# Pure_QUA_SMD_V2_1.net
KiCad netlist of a schematic drawn in EAGLE
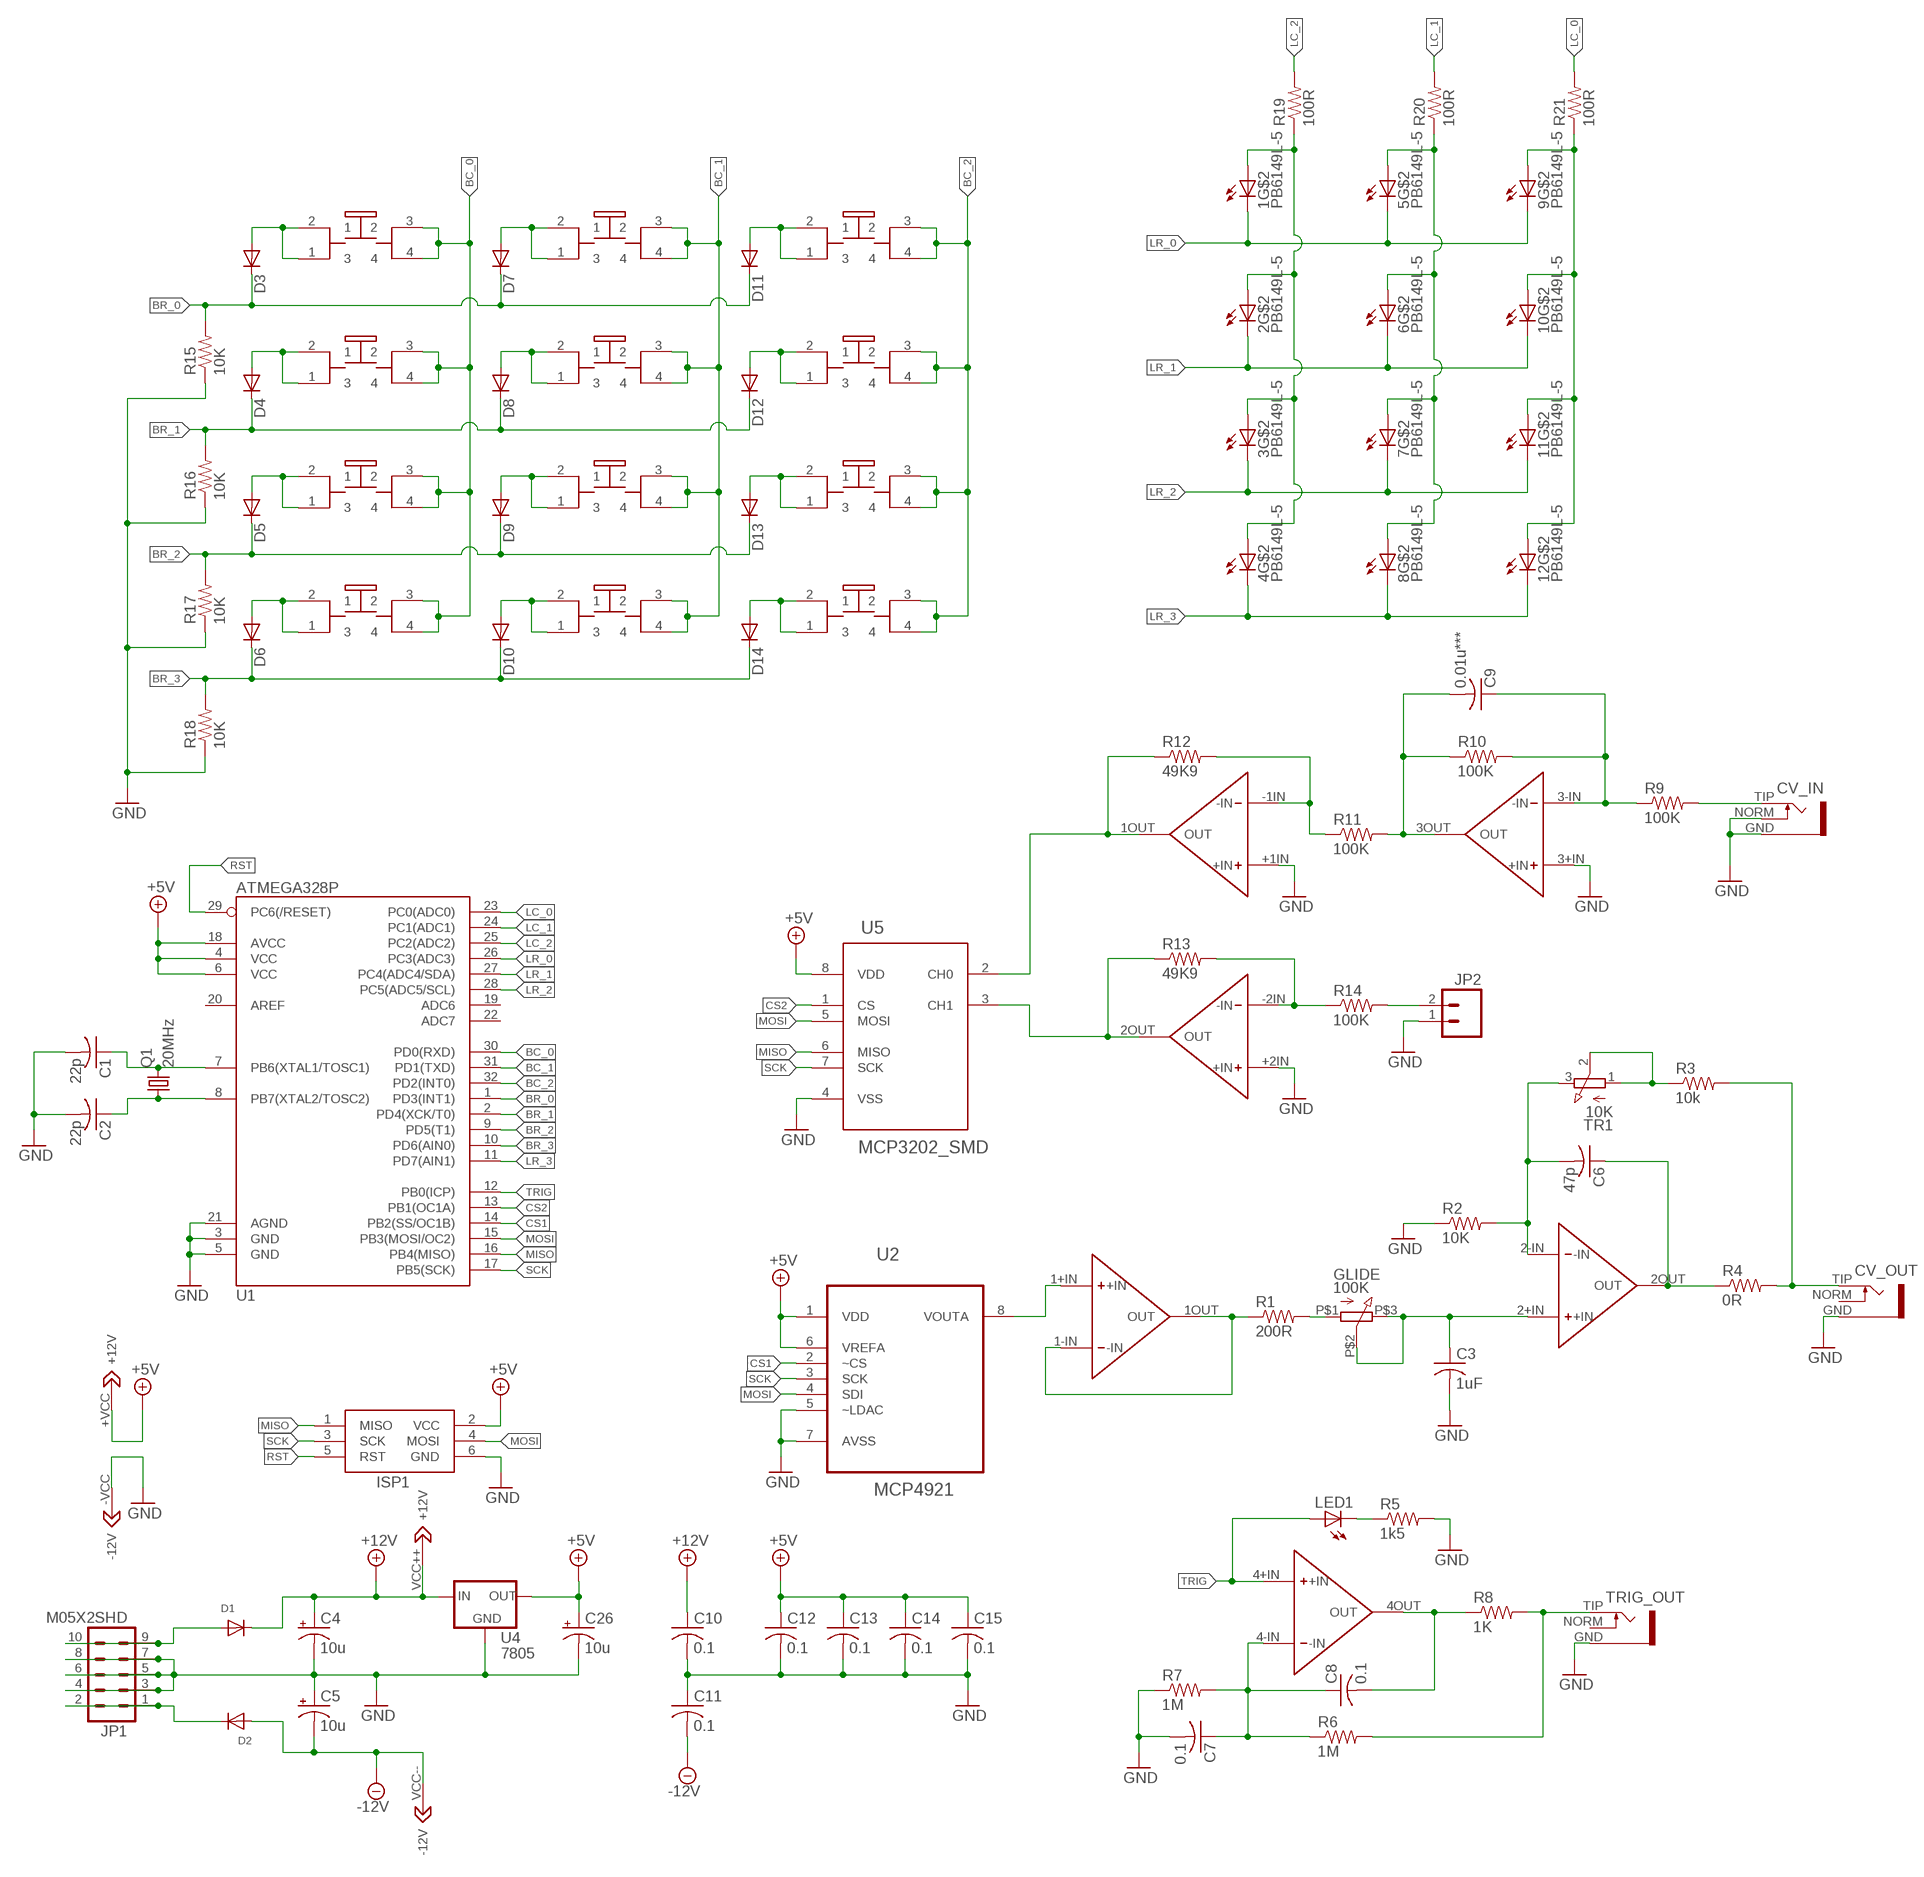
[diagram p0: schematic, sheet 1]

(export (version "E")
  (design (tool "Eeschema 10.0.6"))
  (components
    (comp (ref "1")
      (value "PB6149L-5")
      (footprint "eagle-import:PB6149L")
      (libsource (lib "eagle-import") (part "PB6149L-5"))
    )
    (comp (ref "2")
      (value "PB6149L-5")
      (footprint "eagle-import:PB6149L")
      (libsource (lib "eagle-import") (part "PB6149L-5"))
    )
    (comp (ref "3")
      (value "PB6149L-5")
      (footprint "eagle-import:PB6149L")
      (libsource (lib "eagle-import") (part "PB6149L-5"))
    )
    (comp (ref "4")
      (value "PB6149L-5")
      (footprint "eagle-import:PB6149L")
      (libsource (lib "eagle-import") (part "PB6149L-5"))
    )
    (comp (ref "5")
      (value "PB6149L-5")
      (footprint "eagle-import:PB6149L")
      (libsource (lib "eagle-import") (part "PB6149L-5"))
    )
    (comp (ref "6")
      (value "PB6149L-5")
      (footprint "eagle-import:PB6149L")
      (libsource (lib "eagle-import") (part "PB6149L-5"))
    )
    (comp (ref "7")
      (value "PB6149L-5")
      (footprint "eagle-import:PB6149L")
      (libsource (lib "eagle-import") (part "PB6149L-5"))
    )
    (comp (ref "8")
      (value "PB6149L-5")
      (footprint "eagle-import:PB6149L")
      (libsource (lib "eagle-import") (part "PB6149L-5"))
    )
    (comp (ref "9")
      (value "PB6149L-5")
      (footprint "eagle-import:PB6149L")
      (libsource (lib "eagle-import") (part "PB6149L-5"))
    )
    (comp (ref "10")
      (value "PB6149L-5")
      (footprint "eagle-import:PB6149L")
      (libsource (lib "eagle-import") (part "PB6149L-5"))
    )
    (comp (ref "11")
      (value "PB6149L-5")
      (footprint "eagle-import:PB6149L")
      (libsource (lib "eagle-import") (part "PB6149L-5"))
    )
    (comp (ref "12")
      (value "PB6149L-5")
      (footprint "eagle-import:PB6149L")
      (libsource (lib "eagle-import") (part "PB6149L-5"))
    )
    (comp (ref "C1")
      (value "22p")
      (footprint "eagle-import:C0805K")
      (libsource (lib "eagle-import") (part "C-USC0805K"))
    )
    (comp (ref "C2")
      (value "22p")
      (footprint "eagle-import:C0805K")
      (libsource (lib "eagle-import") (part "C-USC0805K"))
    )
    (comp (ref "C3")
      (value "1uF")
      (footprint "eagle-import:C0805K")
      (libsource (lib "eagle-import") (part "C-USC0805K"))
    )
    (comp (ref "C4")
      (value "10u")
      (footprint "eagle-import:153CLV-0505")
      (libsource (lib "eagle-import") (part "CPOL-US153CLV-0505"))
    )
    (comp (ref "C5")
      (value "10u")
      (footprint "eagle-import:153CLV-0505")
      (libsource (lib "eagle-import") (part "CPOL-US153CLV-0505"))
    )
    (comp (ref "C6")
      (value "47p")
      (footprint "eagle-import:C0805K")
      (libsource (lib "eagle-import") (part "C-USC0805K"))
    )
    (comp (ref "C7")
      (value "0.1")
      (footprint "eagle-import:C0805K")
      (libsource (lib "eagle-import") (part "C-USC0805K"))
    )
    (comp (ref "C8")
      (value "0.1")
      (footprint "eagle-import:C0805K")
      (libsource (lib "eagle-import") (part "C-USC0805K"))
    )
    (comp (ref "C9")
      (value "0.01u***")
      (footprint "eagle-import:C0805K")
      (libsource (lib "eagle-import") (part "C-USC0805K"))
    )
    (comp (ref "C10")
      (value "0.1")
      (footprint "eagle-import:C0805K")
      (libsource (lib "eagle-import") (part "C-USC0805K"))
    )
    (comp (ref "C11")
      (value "0.1")
      (footprint "eagle-import:C0805K")
      (libsource (lib "eagle-import") (part "C-USC0805K"))
    )
    (comp (ref "C12")
      (value "0.1")
      (footprint "eagle-import:C0805K")
      (libsource (lib "eagle-import") (part "C-USC0805K"))
    )
    (comp (ref "C13")
      (value "0.1")
      (footprint "eagle-import:C0805K")
      (libsource (lib "eagle-import") (part "C-USC0805K"))
    )
    (comp (ref "C14")
      (value "0.1")
      (footprint "eagle-import:C0805K")
      (libsource (lib "eagle-import") (part "C-USC0805K"))
    )
    (comp (ref "C15")
      (value "0.1")
      (footprint "eagle-import:C0805K")
      (libsource (lib "eagle-import") (part "C-USC0805K"))
    )
    (comp (ref "C26")
      (value "10u")
      (footprint "eagle-import:153CLV-0505")
      (libsource (lib "eagle-import") (part "CPOL-US153CLV-0505"))
    )
    (comp (ref "CV_IN")
      (value "S_JACK")
      (footprint "eagle-import:S_JACK")
      (libsource (lib "eagle-import") (part "S_JACK"))
    )
    (comp (ref "CV_OUT")
      (value "S_JACK")
      (footprint "eagle-import:S_JACK")
      (libsource (lib "eagle-import") (part "S_JACK"))
    )
    (comp (ref "D1")
      (value "DIODESMA")
      (footprint "eagle-import:SMADIODE")
      (libsource (lib "eagle-import") (part "adafruit_DIODESMA"))
    )
    (comp (ref "D2")
      (value "DIODESMA")
      (footprint "eagle-import:SMADIODE")
      (libsource (lib "eagle-import") (part "adafruit_DIODESMA"))
    )
    (comp (ref "D3")
      (value "DIODESOD")
      (footprint "eagle-import:SOD-323")
      (libsource (lib "eagle-import") (part "DIODESOD"))
    )
    (comp (ref "D4")
      (value "DIODESOD")
      (footprint "eagle-import:SOD-323")
      (libsource (lib "eagle-import") (part "DIODESOD"))
    )
    (comp (ref "D5")
      (value "DIODESOD")
      (footprint "eagle-import:SOD-323")
      (libsource (lib "eagle-import") (part "DIODESOD"))
    )
    (comp (ref "D6")
      (value "DIODESOD")
      (footprint "eagle-import:SOD-323")
      (libsource (lib "eagle-import") (part "DIODESOD"))
    )
    (comp (ref "D7")
      (value "DIODESOD")
      (footprint "eagle-import:SOD-323")
      (libsource (lib "eagle-import") (part "DIODESOD"))
    )
    (comp (ref "D8")
      (value "DIODESOD")
      (footprint "eagle-import:SOD-323")
      (libsource (lib "eagle-import") (part "DIODESOD"))
    )
    (comp (ref "D9")
      (value "DIODESOD")
      (footprint "eagle-import:SOD-323")
      (libsource (lib "eagle-import") (part "DIODESOD"))
    )
    (comp (ref "D10")
      (value "DIODESOD")
      (footprint "eagle-import:SOD-323")
      (libsource (lib "eagle-import") (part "DIODESOD"))
    )
    (comp (ref "D11")
      (value "DIODESOD")
      (footprint "eagle-import:SOD-323")
      (libsource (lib "eagle-import") (part "DIODESOD"))
    )
    (comp (ref "D12")
      (value "DIODESOD")
      (footprint "eagle-import:SOD-323")
      (libsource (lib "eagle-import") (part "DIODESOD"))
    )
    (comp (ref "D13")
      (value "DIODESOD")
      (footprint "eagle-import:SOD-323")
      (libsource (lib "eagle-import") (part "DIODESOD"))
    )
    (comp (ref "D14")
      (value "DIODESOD")
      (footprint "eagle-import:SOD-323")
      (libsource (lib "eagle-import") (part "DIODESOD"))
    )
    (comp (ref "GLIDE")
      (value "100K")
      (footprint "eagle-import:Q-POT")
      (libsource (lib "eagle-import") (part "Q-POT"))
    )
    (comp (ref "ISP1")
      (value "AVRISP-6")
      (footprint "eagle-import:AVRISP")
      (libsource (lib "eagle-import") (part "AVRISP-6"))
    )
    (comp (ref "JP1")
      (value "M05X2SHD")
      (footprint "eagle-import:2X5-SHROUDED")
      (libsource (lib "eagle-import") (part "M05X2SHD"))
    )
    (comp (ref "JP2")
      (value "M02PTH")
      (footprint "eagle-import:1X02")
      (libsource (lib "eagle-import") (part "M02PTH"))
    )
    (comp (ref "LED1")
      (value "LED5MM")
      (footprint "eagle-import:LED5MM")
      (libsource (lib "eagle-import") (part "LED5MM"))
    )
    (comp (ref "Q1")
      (value "20MHz")
      (footprint "eagle-import:HC49UP")
      (libsource (lib "eagle-import") (part "CRYSTALHC49UP"))
    )
    (comp (ref "R1")
      (value "200R")
      (footprint "eagle-import:R0805")
      (libsource (lib "eagle-import") (part "R-US_R0805"))
    )
    (comp (ref "R2")
      (value "10K")
      (footprint "eagle-import:R0805")
      (libsource (lib "eagle-import") (part "R-US_R0805"))
    )
    (comp (ref "R3")
      (value "10k")
      (footprint "eagle-import:R0805")
      (libsource (lib "eagle-import") (part "R-US_R0805"))
    )
    (comp (ref "R4")
      (value "0R")
      (footprint "eagle-import:R0805")
      (libsource (lib "eagle-import") (part "R-US_R0805"))
    )
    (comp (ref "R5")
      (value "1k5")
      (footprint "eagle-import:R0805")
      (libsource (lib "eagle-import") (part "R-US_R0805"))
    )
    (comp (ref "R6")
      (value "1M")
      (footprint "eagle-import:R0805")
      (libsource (lib "eagle-import") (part "R-US_R0805"))
    )
    (comp (ref "R7")
      (value "1M")
      (footprint "eagle-import:R0805")
      (libsource (lib "eagle-import") (part "R-US_R0805"))
    )
    (comp (ref "R8")
      (value "1K")
      (footprint "eagle-import:R0805")
      (libsource (lib "eagle-import") (part "R-US_R0805"))
    )
    (comp (ref "R9")
      (value "100K")
      (footprint "eagle-import:R0805")
      (libsource (lib "eagle-import") (part "R-US_R0805"))
    )
    (comp (ref "R10")
      (value "100K")
      (footprint "eagle-import:R0805")
      (libsource (lib "eagle-import") (part "R-US_R0805"))
    )
    (comp (ref "R11")
      (value "100K")
      (footprint "eagle-import:R0805")
      (libsource (lib "eagle-import") (part "R-US_R0805"))
    )
    (comp (ref "R12")
      (value "49K9")
      (footprint "eagle-import:R0805")
      (libsource (lib "eagle-import") (part "R-US_R0805"))
    )
    (comp (ref "R13")
      (value "49K9")
      (footprint "eagle-import:R0805")
      (libsource (lib "eagle-import") (part "R-US_R0805"))
    )
    (comp (ref "R14")
      (value "100K")
      (footprint "eagle-import:R0805")
      (libsource (lib "eagle-import") (part "R-US_R0805"))
    )
    (comp (ref "R15")
      (value "10K")
      (footprint "eagle-import:R0805")
      (libsource (lib "eagle-import") (part "R-US_R0805"))
    )
    (comp (ref "R16")
      (value "10K")
      (footprint "eagle-import:R0805")
      (libsource (lib "eagle-import") (part "R-US_R0805"))
    )
    (comp (ref "R17")
      (value "10K")
      (footprint "eagle-import:R0805")
      (libsource (lib "eagle-import") (part "R-US_R0805"))
    )
    (comp (ref "R18")
      (value "10K")
      (footprint "eagle-import:R0805")
      (libsource (lib "eagle-import") (part "R-US_R0805"))
    )
    (comp (ref "R19")
      (value "100R")
      (footprint "eagle-import:R0805")
      (libsource (lib "eagle-import") (part "R-US_R0805"))
    )
    (comp (ref "R20")
      (value "100R")
      (footprint "eagle-import:R0805")
      (libsource (lib "eagle-import") (part "R-US_R0805"))
    )
    (comp (ref "R21")
      (value "100R")
      (footprint "eagle-import:R0805")
      (libsource (lib "eagle-import") (part "R-US_R0805"))
    )
    (comp (ref "TR1")
      (value "10K")
      (footprint "eagle-import:TRIM_3269W")
      (libsource (lib "eagle-import") (part "TRIM_3269W"))
    )
    (comp (ref "TRIG_OUT")
      (value "S_JACK")
      (footprint "eagle-import:S_JACK")
      (libsource (lib "eagle-import") (part "S_JACK"))
    )
    (comp (ref "U1")
      (value "ATMEGA328P")
      (footprint "eagle-import:TQFP32-08")
      (libsource (lib "eagle-import") (part "ATMEGA328_SMT"))
    )
    (comp (ref "U2")
      (value "MCP4921")
      (footprint "eagle-import:SOIC8")
      (libsource (lib "eagle-import") (part "MCP4921"))
    )
    (comp (ref "U3")
      (value "QUAD_OPAMP")
      (footprint "eagle-import:QUAD_OPAMP")
      (libsource (lib "eagle-import") (part "QUAD_OPAMP"))
    )
    (comp (ref "U4")
      (value "7805")
      (footprint "eagle-import:V-REG")
      (libsource (lib "eagle-import") (part "V-REG"))
    )
    (comp (ref "U5")
      (value "MCP3202_SMD")
      (footprint "eagle-import:SOIC--8")
      (libsource (lib "eagle-import") (part "MCP3202_SMD"))
    )
    (comp (ref "U6")
      (value "DUAL_OPAMP")
      (footprint "eagle-import:DUAL_OPAMP")
      (libsource (lib "eagle-import") (part "DUAL_OPAMP"))
    )
  )
  (nets
    (net (code "1") (name "+5V") (class "Default")
      (node (ref "C12") (pin "1") (pinfunction "1_1") (pintype "passive"))
      (node (ref "C13") (pin "1") (pinfunction "1_1") (pintype "passive"))
      (node (ref "C14") (pin "1") (pinfunction "1_1") (pintype "passive"))
      (node (ref "C15") (pin "1") (pinfunction "1_1") (pintype "passive"))
      (node (ref "C26") (pin "+") (pinfunction "+_+") (pintype "passive"))
      (node (ref "ISP1") (pin "2") (pinfunction "VCC_2") (pintype "power_in"))
      (node (ref "U1") (pin "18") (pinfunction "AVCC_18") (pintype "bidirectional"))
      (node (ref "U1") (pin "4") (pinfunction "VCC_4") (pintype "bidirectional"))
      (node (ref "U1") (pin "6") (pinfunction "VCC_6") (pintype "bidirectional"))
      (node (ref "U2") (pin "1") (pinfunction "VDD_1") (pintype "power_in"))
      (node (ref "U2") (pin "6") (pinfunction "VREFA_6") (pintype "input"))
      (node (ref "U4") (pin "3") (pinfunction "OUT_3") (pintype "passive"))
      (node (ref "U5") (pin "8") (pinfunction "VDD_8") (pintype "bidirectional"))
      (node (ref "U6") (pin "+VCC") (pinfunction "+12V_+VCC") (pintype "bidirectional"))
    )
    (net (code "2") (name "+12V") (class "Default")
      (node (ref "C10") (pin "1") (pinfunction "1_1") (pintype "passive"))
      (node (ref "C4") (pin "+") (pinfunction "+_+") (pintype "passive"))
      (node (ref "D1") (pin "C") (pinfunction "C_C") (pintype "passive"))
      (node (ref "U3") (pin "VCC++") (pinfunction "+12V_VCC++") (pintype "bidirectional"))
      (node (ref "U4") (pin "1") (pinfunction "IN_1") (pintype "input"))
    )
    (net (code "3") (name "-12V") (class "Default")
      (node (ref "C11") (pin "2") (pinfunction "2_2") (pintype "passive"))
      (node (ref "C5") (pin "-") (pinfunction "-_-") (pintype "passive"))
      (node (ref "D2") (pin "A") (pinfunction "A_A") (pintype "passive"))
      (node (ref "U3") (pin "VCC--") (pinfunction "-12V_VCC--") (pintype "bidirectional"))
    )
    (net (code "4") (name "BC_0") (class "Default")
      (node (ref "1") (pin "3") (pinfunction "2_3") (pintype "bidirectional"))
      (node (ref "1") (pin "4") (pinfunction "4_4") (pintype "bidirectional"))
      (node (ref "2") (pin "3") (pinfunction "2_3") (pintype "bidirectional"))
      (node (ref "2") (pin "4") (pinfunction "4_4") (pintype "bidirectional"))
      (node (ref "3") (pin "3") (pinfunction "2_3") (pintype "bidirectional"))
      (node (ref "3") (pin "4") (pinfunction "4_4") (pintype "bidirectional"))
      (node (ref "4") (pin "3") (pinfunction "2_3") (pintype "bidirectional"))
      (node (ref "4") (pin "4") (pinfunction "4_4") (pintype "bidirectional"))
      (node (ref "U1") (pin "30") (pinfunction "PD0(RXD)_30") (pintype "bidirectional"))
    )
    (net (code "5") (name "BC_1") (class "Default")
      (node (ref "5") (pin "3") (pinfunction "2_3") (pintype "bidirectional"))
      (node (ref "5") (pin "4") (pinfunction "4_4") (pintype "bidirectional"))
      (node (ref "6") (pin "3") (pinfunction "2_3") (pintype "bidirectional"))
      (node (ref "6") (pin "4") (pinfunction "4_4") (pintype "bidirectional"))
      (node (ref "7") (pin "3") (pinfunction "2_3") (pintype "bidirectional"))
      (node (ref "7") (pin "4") (pinfunction "4_4") (pintype "bidirectional"))
      (node (ref "8") (pin "3") (pinfunction "2_3") (pintype "bidirectional"))
      (node (ref "8") (pin "4") (pinfunction "4_4") (pintype "bidirectional"))
      (node (ref "U1") (pin "31") (pinfunction "PD1(TXD)_31") (pintype "bidirectional"))
    )
    (net (code "6") (name "BC_2") (class "Default")
      (node (ref "10") (pin "3") (pinfunction "2_3") (pintype "bidirectional"))
      (node (ref "10") (pin "4") (pinfunction "4_4") (pintype "bidirectional"))
      (node (ref "11") (pin "3") (pinfunction "2_3") (pintype "bidirectional"))
      (node (ref "11") (pin "4") (pinfunction "4_4") (pintype "bidirectional"))
      (node (ref "12") (pin "3") (pinfunction "2_3") (pintype "bidirectional"))
      (node (ref "12") (pin "4") (pinfunction "4_4") (pintype "bidirectional"))
      (node (ref "9") (pin "3") (pinfunction "2_3") (pintype "bidirectional"))
      (node (ref "9") (pin "4") (pinfunction "4_4") (pintype "bidirectional"))
      (node (ref "U1") (pin "32") (pinfunction "PD2(INT0)_32") (pintype "bidirectional"))
    )
    (net (code "7") (name "BR_0") (class "Default")
      (node (ref "D11") (pin "1") (pinfunction "C_1") (pintype "passive"))
      (node (ref "D3") (pin "1") (pinfunction "C_1") (pintype "passive"))
      (node (ref "D7") (pin "1") (pinfunction "C_1") (pintype "passive"))
      (node (ref "R15") (pin "2") (pinfunction "2_2") (pintype "passive"))
      (node (ref "U1") (pin "1") (pinfunction "PD3(INT1)_1") (pintype "bidirectional"))
    )
    (net (code "8") (name "BR_1") (class "Default")
      (node (ref "D12") (pin "1") (pinfunction "C_1") (pintype "passive"))
      (node (ref "D4") (pin "1") (pinfunction "C_1") (pintype "passive"))
      (node (ref "D8") (pin "1") (pinfunction "C_1") (pintype "passive"))
      (node (ref "R16") (pin "2") (pinfunction "2_2") (pintype "passive"))
      (node (ref "U1") (pin "2") (pinfunction "PD4(XCK/T0)_2") (pintype "bidirectional"))
    )
    (net (code "9") (name "BR_2") (class "Default")
      (node (ref "D13") (pin "1") (pinfunction "C_1") (pintype "passive"))
      (node (ref "D5") (pin "1") (pinfunction "C_1") (pintype "passive"))
      (node (ref "D9") (pin "1") (pinfunction "C_1") (pintype "passive"))
      (node (ref "R17") (pin "2") (pinfunction "2_2") (pintype "passive"))
      (node (ref "U1") (pin "9") (pinfunction "PD5(T1)_9") (pintype "bidirectional"))
    )
    (net (code "10") (name "BR_3") (class "Default")
      (node (ref "D10") (pin "1") (pinfunction "C_1") (pintype "passive"))
      (node (ref "D14") (pin "1") (pinfunction "C_1") (pintype "passive"))
      (node (ref "D6") (pin "1") (pinfunction "C_1") (pintype "passive"))
      (node (ref "R18") (pin "2") (pinfunction "2_2") (pintype "passive"))
      (node (ref "U1") (pin "10") (pinfunction "PD6(AIN0)_10") (pintype "bidirectional"))
    )
    (net (code "11") (name "CS1") (class "Default")
      (node (ref "U1") (pin "14") (pinfunction "PB2(SS/OC1B)_14") (pintype "bidirectional"))
      (node (ref "U2") (pin "2") (pinfunction "~{CS}_2") (pintype "input"))
    )
    (net (code "12") (name "CS2") (class "Default")
      (node (ref "U1") (pin "13") (pinfunction "PB1(OC1A)_13") (pintype "bidirectional"))
      (node (ref "U5") (pin "1") (pinfunction "CS_1") (pintype "bidirectional"))
    )
    (net (code "13") (name "GND") (class "Default")
      (node (ref "C1") (pin "2") (pinfunction "2_2") (pintype "passive"))
      (node (ref "C10") (pin "2") (pinfunction "2_2") (pintype "passive"))
      (node (ref "C11") (pin "1") (pinfunction "1_1") (pintype "passive"))
      (node (ref "C12") (pin "2") (pinfunction "2_2") (pintype "passive"))
      (node (ref "C13") (pin "2") (pinfunction "2_2") (pintype "passive"))
      (node (ref "C14") (pin "2") (pinfunction "2_2") (pintype "passive"))
      (node (ref "C15") (pin "2") (pinfunction "2_2") (pintype "passive"))
      (node (ref "C2") (pin "2") (pinfunction "2_2") (pintype "passive"))
      (node (ref "C26") (pin "-") (pinfunction "-_-") (pintype "passive"))
      (node (ref "C3") (pin "2") (pinfunction "2_2") (pintype "passive"))
      (node (ref "C4") (pin "-") (pinfunction "-_-") (pintype "passive"))
      (node (ref "C5") (pin "+") (pinfunction "+_+") (pintype "passive"))
      (node (ref "C7") (pin "2") (pinfunction "2_2") (pintype "passive"))
      (node (ref "CV_IN") (pin "GND") (pinfunction "GND_GND") (pintype "passive"))
      (node (ref "CV_IN") (pin "NORM") (pinfunction "NORM_NORM") (pintype "passive"))
      (node (ref "CV_OUT") (pin "GND") (pinfunction "GND_GND") (pintype "passive"))
      (node (ref "ISP1") (pin "6") (pinfunction "GND_6") (pintype "power_in"))
      (node (ref "JP1") (pin "3") (pinfunction "3_3") (pintype "passive"))
      (node (ref "JP1") (pin "4") (pinfunction "4_4") (pintype "passive"))
      (node (ref "JP1") (pin "5") (pinfunction "5_5") (pintype "passive"))
      (node (ref "JP1") (pin "6") (pinfunction "6_6") (pintype "passive"))
      (node (ref "JP1") (pin "7") (pinfunction "7_7") (pintype "passive"))
      (node (ref "JP1") (pin "8") (pinfunction "8_8") (pintype "passive"))
      (node (ref "JP2") (pin "1") (pinfunction "1_1") (pintype "passive"))
      (node (ref "R15") (pin "1") (pinfunction "1_1") (pintype "passive"))
      (node (ref "R16") (pin "1") (pinfunction "1_1") (pintype "passive"))
      (node (ref "R17") (pin "1") (pinfunction "1_1") (pintype "passive"))
      (node (ref "R18") (pin "1") (pinfunction "1_1") (pintype "passive"))
      (node (ref "R2") (pin "1") (pinfunction "1_1") (pintype "passive"))
      (node (ref "R5") (pin "2") (pinfunction "2_2") (pintype "passive"))
      (node (ref "R7") (pin "1") (pinfunction "1_1") (pintype "passive"))
      (node (ref "TRIG_OUT") (pin "GND") (pinfunction "GND_GND") (pintype "passive"))
      (node (ref "U1") (pin "21") (pinfunction "AGND_21") (pintype "bidirectional"))
      (node (ref "U1") (pin "3") (pinfunction "GND_3") (pintype "bidirectional"))
      (node (ref "U1") (pin "5") (pinfunction "GND_5") (pintype "bidirectional"))
      (node (ref "U2") (pin "5") (pinfunction "~{LDAC}_5") (pintype "input"))
      (node (ref "U2") (pin "7") (pinfunction "AVSS_7") (pintype "passive"))
      (node (ref "U3") (pin "3+IN") (pinfunction "+IN_3+IN") (pintype "bidirectional"))
      (node (ref "U4") (pin "4") (pinfunction "GND_4") (pintype "input"))
      (node (ref "U5") (pin "4") (pinfunction "VSS_4") (pintype "bidirectional"))
      (node (ref "U6") (pin "+1IN") (pinfunction "+IN_+1IN") (pintype "bidirectional"))
      (node (ref "U6") (pin "+2IN") (pinfunction "+IN_+2IN") (pintype "bidirectional"))
      (node (ref "U6") (pin "-VCC") (pinfunction "-12V_-VCC") (pintype "bidirectional"))
    )
    (net (code "14") (name "LC_0") (class "Default")
      (node (ref "R21") (pin "2") (pinfunction "2_2") (pintype "passive"))
      (node (ref "U1") (pin "23") (pinfunction "PC0(ADC0)_23") (pintype "bidirectional"))
    )
    (net (code "15") (name "LC_1") (class "Default")
      (node (ref "R20") (pin "2") (pinfunction "2_2") (pintype "passive"))
      (node (ref "U1") (pin "24") (pinfunction "PC1(ADC1)_24") (pintype "bidirectional"))
    )
    (net (code "16") (name "LC_2") (class "Default")
      (node (ref "R19") (pin "2") (pinfunction "2_2") (pintype "passive"))
      (node (ref "U1") (pin "25") (pinfunction "PC2(ADC2)_25") (pintype "bidirectional"))
    )
    (net (code "17") (name "LR_0") (class "Default")
      (node (ref "1") (pin "K") (pinfunction "C_K") (pintype "passive"))
      (node (ref "5") (pin "K") (pinfunction "C_K") (pintype "passive"))
      (node (ref "9") (pin "K") (pinfunction "C_K") (pintype "passive"))
      (node (ref "U1") (pin "26") (pinfunction "PC3(ADC3)_26") (pintype "bidirectional"))
    )
    (net (code "18") (name "LR_1") (class "Default")
      (node (ref "10") (pin "K") (pinfunction "C_K") (pintype "passive"))
      (node (ref "2") (pin "K") (pinfunction "C_K") (pintype "passive"))
      (node (ref "6") (pin "K") (pinfunction "C_K") (pintype "passive"))
      (node (ref "U1") (pin "27") (pinfunction "PC4(ADC4/SDA)_27") (pintype "bidirectional"))
    )
    (net (code "19") (name "LR_2") (class "Default")
      (node (ref "11") (pin "K") (pinfunction "C_K") (pintype "passive"))
      (node (ref "3") (pin "K") (pinfunction "C_K") (pintype "passive"))
      (node (ref "7") (pin "K") (pinfunction "C_K") (pintype "passive"))
      (node (ref "U1") (pin "28") (pinfunction "PC5(ADC5/SCL)_28") (pintype "bidirectional"))
    )
    (net (code "20") (name "LR_3") (class "Default")
      (node (ref "12") (pin "K") (pinfunction "C_K") (pintype "passive"))
      (node (ref "4") (pin "K") (pinfunction "C_K") (pintype "passive"))
      (node (ref "8") (pin "K") (pinfunction "C_K") (pintype "passive"))
      (node (ref "U1") (pin "11") (pinfunction "PD7(AIN1)_11") (pintype "bidirectional"))
    )
    (net (code "21") (name "MISO") (class "Default")
      (node (ref "ISP1") (pin "1") (pinfunction "MISO_1") (pintype "input"))
      (node (ref "U1") (pin "16") (pinfunction "PB4(MISO)_16") (pintype "bidirectional"))
      (node (ref "U5") (pin "6") (pinfunction "MISO_6") (pintype "bidirectional"))
    )
    (net (code "22") (name "MOSI") (class "Default")
      (node (ref "ISP1") (pin "4") (pinfunction "MOSI_4") (pintype "output"))
      (node (ref "U1") (pin "15") (pinfunction "PB3(MOSI/OC2)_15") (pintype "bidirectional"))
      (node (ref "U2") (pin "4") (pinfunction "SDI_4") (pintype "input"))
      (node (ref "U5") (pin "5") (pinfunction "MOSI_5") (pintype "bidirectional"))
    )
    (net (code "23") (name "Net-(1-PadA)") (class "Default")
      (node (ref "1") (pin "A") (pinfunction "A_A") (pintype "passive"))
      (node (ref "2") (pin "A") (pinfunction "A_A") (pintype "passive"))
      (node (ref "3") (pin "A") (pinfunction "A_A") (pintype "passive"))
      (node (ref "4") (pin "A") (pinfunction "A_A") (pintype "passive"))
      (node (ref "R19") (pin "1") (pinfunction "1_1") (pintype "passive"))
    )
    (net (code "24") (name "Net-(1A-1)") (class "Default")
      (node (ref "1") (pin "1") (pinfunction "3_1") (pintype "bidirectional"))
      (node (ref "1") (pin "2") (pinfunction "1_2") (pintype "bidirectional"))
      (node (ref "D3") (pin "2") (pinfunction "A_2") (pintype "passive"))
    )
    (net (code "25") (name "Net-(2A-1)") (class "Default")
      (node (ref "2") (pin "1") (pinfunction "3_1") (pintype "bidirectional"))
      (node (ref "2") (pin "2") (pinfunction "1_2") (pintype "bidirectional"))
      (node (ref "D4") (pin "2") (pinfunction "A_2") (pintype "passive"))
    )
    (net (code "26") (name "Net-(3A-1)") (class "Default")
      (node (ref "3") (pin "1") (pinfunction "3_1") (pintype "bidirectional"))
      (node (ref "3") (pin "2") (pinfunction "1_2") (pintype "bidirectional"))
      (node (ref "D5") (pin "2") (pinfunction "A_2") (pintype "passive"))
    )
    (net (code "27") (name "Net-(4A-1)") (class "Default")
      (node (ref "4") (pin "1") (pinfunction "3_1") (pintype "bidirectional"))
      (node (ref "4") (pin "2") (pinfunction "1_2") (pintype "bidirectional"))
      (node (ref "D6") (pin "2") (pinfunction "A_2") (pintype "passive"))
    )
    (net (code "28") (name "Net-(5-PadA)") (class "Default")
      (node (ref "5") (pin "A") (pinfunction "A_A") (pintype "passive"))
      (node (ref "6") (pin "A") (pinfunction "A_A") (pintype "passive"))
      (node (ref "7") (pin "A") (pinfunction "A_A") (pintype "passive"))
      (node (ref "8") (pin "A") (pinfunction "A_A") (pintype "passive"))
      (node (ref "R20") (pin "1") (pinfunction "1_1") (pintype "passive"))
    )
    (net (code "29") (name "Net-(5A-1)") (class "Default")
      (node (ref "5") (pin "1") (pinfunction "3_1") (pintype "bidirectional"))
      (node (ref "5") (pin "2") (pinfunction "1_2") (pintype "bidirectional"))
      (node (ref "D7") (pin "2") (pinfunction "A_2") (pintype "passive"))
    )
    (net (code "30") (name "Net-(6A-1)") (class "Default")
      (node (ref "6") (pin "1") (pinfunction "3_1") (pintype "bidirectional"))
      (node (ref "6") (pin "2") (pinfunction "1_2") (pintype "bidirectional"))
      (node (ref "D8") (pin "2") (pinfunction "A_2") (pintype "passive"))
    )
    (net (code "31") (name "Net-(7A-1)") (class "Default")
      (node (ref "7") (pin "1") (pinfunction "3_1") (pintype "bidirectional"))
      (node (ref "7") (pin "2") (pinfunction "1_2") (pintype "bidirectional"))
      (node (ref "D9") (pin "2") (pinfunction "A_2") (pintype "passive"))
    )
    (net (code "32") (name "Net-(8A-1)") (class "Default")
      (node (ref "8") (pin "1") (pinfunction "3_1") (pintype "bidirectional"))
      (node (ref "8") (pin "2") (pinfunction "1_2") (pintype "bidirectional"))
      (node (ref "D10") (pin "2") (pinfunction "A_2") (pintype "passive"))
    )
    (net (code "33") (name "Net-(9A-1)") (class "Default")
      (node (ref "9") (pin "1") (pinfunction "3_1") (pintype "bidirectional"))
      (node (ref "9") (pin "2") (pinfunction "1_2") (pintype "bidirectional"))
      (node (ref "D11") (pin "2") (pinfunction "A_2") (pintype "passive"))
    )
    (net (code "34") (name "Net-(10-PadA)") (class "Default")
      (node (ref "10") (pin "A") (pinfunction "A_A") (pintype "passive"))
      (node (ref "11") (pin "A") (pinfunction "A_A") (pintype "passive"))
      (node (ref "12") (pin "A") (pinfunction "A_A") (pintype "passive"))
      (node (ref "9") (pin "A") (pinfunction "A_A") (pintype "passive"))
      (node (ref "R21") (pin "1") (pinfunction "1_1") (pintype "passive"))
    )
    (net (code "35") (name "Net-(10A-1)") (class "Default")
      (node (ref "10") (pin "1") (pinfunction "3_1") (pintype "bidirectional"))
      (node (ref "10") (pin "2") (pinfunction "1_2") (pintype "bidirectional"))
      (node (ref "D12") (pin "2") (pinfunction "A_2") (pintype "passive"))
    )
    (net (code "36") (name "Net-(11A-1)") (class "Default")
      (node (ref "11") (pin "1") (pinfunction "3_1") (pintype "bidirectional"))
      (node (ref "11") (pin "2") (pinfunction "1_2") (pintype "bidirectional"))
      (node (ref "D13") (pin "2") (pinfunction "A_2") (pintype "passive"))
    )
    (net (code "37") (name "Net-(12A-1)") (class "Default")
      (node (ref "12") (pin "1") (pinfunction "3_1") (pintype "bidirectional"))
      (node (ref "12") (pin "2") (pinfunction "1_2") (pintype "bidirectional"))
      (node (ref "D14") (pin "2") (pinfunction "A_2") (pintype "passive"))
    )
    (net (code "38") (name "Net-(CV_IN-PadTIP)") (class "Default")
      (node (ref "CV_IN") (pin "TIP") (pinfunction "TIP_TIP") (pintype "passive"))
      (node (ref "R9") (pin "2") (pinfunction "2_2") (pintype "passive"))
    )
    (net (code "39") (name "Net-(CV_OUT-PadTIP)") (class "Default")
      (node (ref "CV_OUT") (pin "TIP") (pinfunction "TIP_TIP") (pintype "passive"))
      (node (ref "R3") (pin "2") (pinfunction "2_2") (pintype "passive"))
      (node (ref "R4") (pin "2") (pinfunction "2_2") (pintype "passive"))
    )
    (net (code "40") (name "Net-(D1-PadA)") (class "Default")
      (node (ref "D1") (pin "A") (pinfunction "A_A") (pintype "passive"))
      (node (ref "JP1") (pin "10") (pinfunction "10_10") (pintype "passive"))
      (node (ref "JP1") (pin "9") (pinfunction "9_9") (pintype "passive"))
    )
    (net (code "41") (name "Net-(D2-PadC)") (class "Default")
      (node (ref "D2") (pin "C") (pinfunction "C_C") (pintype "passive"))
      (node (ref "JP1") (pin "1") (pinfunction "1_1") (pintype "passive"))
      (node (ref "JP1") (pin "2") (pinfunction "2_2") (pintype "passive"))
    )
    (net (code "42") (name "Net-(GLIDE-1)") (class "Default")
      (node (ref "GLIDE") (pin "P$1") (pinfunction "1_P$1") (pintype "passive"))
      (node (ref "R1") (pin "2") (pinfunction "2_2") (pintype "passive"))
    )
    (net (code "43") (name "Net-(GLIDE-2)") (class "Default")
      (node (ref "C3") (pin "1") (pinfunction "1_1") (pintype "passive"))
      (node (ref "GLIDE") (pin "P$2") (pinfunction "2_P$2") (pintype "passive"))
      (node (ref "GLIDE") (pin "P$3") (pinfunction "3_P$3") (pintype "passive"))
      (node (ref "U3") (pin "2+IN") (pinfunction "+IN_2+IN") (pintype "bidirectional"))
    )
    (net (code "44") (name "Net-(JP2-Pad2)") (class "Default")
      (node (ref "JP2") (pin "2") (pinfunction "2_2") (pintype "passive"))
      (node (ref "R14") (pin "2") (pinfunction "2_2") (pintype "passive"))
    )
    (net (code "45") (name "Net-(LED1-C)") (class "Default")
      (node (ref "LED1") (pin "K") (pinfunction "C_K") (pintype "passive"))
      (node (ref "R5") (pin "1") (pinfunction "1_1") (pintype "passive"))
    )
    (net (code "46") (name "Net-(R3-Pad1)") (class "Default")
      (node (ref "R3") (pin "1") (pinfunction "1_1") (pintype "passive"))
      (node (ref "TR1") (pin "1") (pinfunction "1_1") (pintype "passive"))
      (node (ref "TR1") (pin "2") (pinfunction "2_2") (pintype "passive"))
    )
    (net (code "47") (name "Net-(R6-Pad2)") (class "Default")
      (node (ref "R6") (pin "2") (pinfunction "2_2") (pintype "passive"))
      (node (ref "R8") (pin "2") (pinfunction "2_2") (pintype "passive"))
      (node (ref "TRIG_OUT") (pin "TIP") (pinfunction "TIP_TIP") (pintype "passive"))
    )
    (net (code "48") (name "Net-(U1-PB6(XTAL1{slash}TOSC1))") (class "Default")
      (node (ref "C1") (pin "1") (pinfunction "1_1") (pintype "passive"))
      (node (ref "Q1") (pin "2") (pinfunction "2_2") (pintype "passive"))
      (node (ref "U1") (pin "7") (pinfunction "PB6(XTAL1/TOSC1)_7") (pintype "bidirectional"))
    )
    (net (code "49") (name "Net-(U1-PB7(XTAL2{slash}TOSC2))") (class "Default")
      (node (ref "C2") (pin "1") (pinfunction "1_1") (pintype "passive"))
      (node (ref "Q1") (pin "1") (pinfunction "1_1") (pintype "passive"))
      (node (ref "U1") (pin "8") (pinfunction "PB7(XTAL2/TOSC2)_8") (pintype "bidirectional"))
    )
    (net (code "50") (name "Net-(U2-VOUTA)") (class "Default")
      (node (ref "U2") (pin "8") (pinfunction "VOUTA_8") (pintype "output"))
      (node (ref "U3") (pin "1+IN") (pinfunction "+IN_1+IN") (pintype "bidirectional"))
    )
    (net (code "51") (name "Net-(U3A--IN)") (class "Default")
      (node (ref "R1") (pin "1") (pinfunction "1_1") (pintype "passive"))
      (node (ref "U3") (pin "1-IN") (pinfunction "-IN_1-IN") (pintype "bidirectional"))
      (node (ref "U3") (pin "1OUT") (pinfunction "OUT_1OUT") (pintype "bidirectional"))
    )
    (net (code "52") (name "Net-(U3B--IN)") (class "Default")
      (node (ref "C6") (pin "2") (pinfunction "2_2") (pintype "passive"))
      (node (ref "R2") (pin "2") (pinfunction "2_2") (pintype "passive"))
      (node (ref "TR1") (pin "3") (pinfunction "3_3") (pintype "passive"))
      (node (ref "U3") (pin "2-IN") (pinfunction "-IN_2-IN") (pintype "bidirectional"))
    )
    (net (code "53") (name "Net-(U3B-OUT)") (class "Default")
      (node (ref "C6") (pin "1") (pinfunction "1_1") (pintype "passive"))
      (node (ref "R4") (pin "1") (pinfunction "1_1") (pintype "passive"))
      (node (ref "U3") (pin "2OUT") (pinfunction "OUT_2OUT") (pintype "bidirectional"))
    )
    (net (code "54") (name "Net-(U3C--IN)") (class "Default")
      (node (ref "C9") (pin "1") (pinfunction "1_1") (pintype "passive"))
      (node (ref "R10") (pin "2") (pinfunction "2_2") (pintype "passive"))
      (node (ref "R9") (pin "1") (pinfunction "1_1") (pintype "passive"))
      (node (ref "U3") (pin "3-IN") (pinfunction "-IN_3-IN") (pintype "bidirectional"))
    )
    (net (code "55") (name "Net-(U3C-OUT)") (class "Default")
      (node (ref "C9") (pin "2") (pinfunction "2_2") (pintype "passive"))
      (node (ref "R10") (pin "1") (pinfunction "1_1") (pintype "passive"))
      (node (ref "R11") (pin "2") (pinfunction "2_2") (pintype "passive"))
      (node (ref "U3") (pin "3OUT") (pinfunction "OUT_3OUT") (pintype "bidirectional"))
    )
    (net (code "56") (name "Net-(U3D--IN)") (class "Default")
      (node (ref "C7") (pin "1") (pinfunction "1_1") (pintype "passive"))
      (node (ref "C8") (pin "1") (pinfunction "1_1") (pintype "passive"))
      (node (ref "R6") (pin "1") (pinfunction "1_1") (pintype "passive"))
      (node (ref "R7") (pin "2") (pinfunction "2_2") (pintype "passive"))
      (node (ref "U3") (pin "4-IN") (pinfunction "-IN_4-IN") (pintype "bidirectional"))
    )
    (net (code "57") (name "Net-(U3D-OUT)") (class "Default")
      (node (ref "C8") (pin "2") (pinfunction "2_2") (pintype "passive"))
      (node (ref "R8") (pin "1") (pinfunction "1_1") (pintype "passive"))
      (node (ref "U3") (pin "4OUT") (pinfunction "OUT_4OUT") (pintype "bidirectional"))
    )
    (net (code "58") (name "Net-(U5-CH0)") (class "Default")
      (node (ref "R12") (pin "1") (pinfunction "1_1") (pintype "passive"))
      (node (ref "U5") (pin "2") (pinfunction "CH0_2") (pintype "bidirectional"))
      (node (ref "U6") (pin "1OUT") (pinfunction "OUT_1OUT") (pintype "bidirectional"))
    )
    (net (code "59") (name "Net-(U5-CH1)") (class "Default")
      (node (ref "R13") (pin "1") (pinfunction "1_1") (pintype "passive"))
      (node (ref "U5") (pin "3") (pinfunction "CH1_3") (pintype "bidirectional"))
      (node (ref "U6") (pin "2OUT") (pinfunction "OUT_2OUT") (pintype "bidirectional"))
    )
    (net (code "60") (name "Net-(U6A--IN)") (class "Default")
      (node (ref "R11") (pin "1") (pinfunction "1_1") (pintype "passive"))
      (node (ref "R12") (pin "2") (pinfunction "2_2") (pintype "passive"))
      (node (ref "U6") (pin "-1IN") (pinfunction "-IN_-1IN") (pintype "bidirectional"))
    )
    (net (code "61") (name "Net-(U6B--IN)") (class "Default")
      (node (ref "R13") (pin "2") (pinfunction "2_2") (pintype "passive"))
      (node (ref "R14") (pin "1") (pinfunction "1_1") (pintype "passive"))
      (node (ref "U6") (pin "-2IN") (pinfunction "-IN_-2IN") (pintype "bidirectional"))
    )
    (net (code "62") (name "RST") (class "Default")
      (node (ref "ISP1") (pin "5") (pinfunction "RST_5") (pintype "output"))
      (node (ref "U1") (pin "29") (pinfunction "PC6(/RESET)_29") (pintype "bidirectional"))
    )
    (net (code "63") (name "SCK") (class "Default")
      (node (ref "ISP1") (pin "3") (pinfunction "SCK_3") (pintype "output"))
      (node (ref "U1") (pin "17") (pinfunction "PB5(SCK)_17") (pintype "bidirectional"))
      (node (ref "U2") (pin "3") (pinfunction "SCK_3") (pintype "input"))
      (node (ref "U5") (pin "7") (pinfunction "SCK_7") (pintype "bidirectional"))
    )
    (net (code "64") (name "TRIG") (class "Default")
      (node (ref "LED1") (pin "A") (pinfunction "A_A") (pintype "passive"))
      (node (ref "U1") (pin "12") (pinfunction "PB0(ICP)_12") (pintype "bidirectional"))
      (node (ref "U3") (pin "4+IN") (pinfunction "+IN_4+IN") (pintype "bidirectional"))
    )
    (net (code "65") (name "unconnected-(CV_OUT-PadNORM)") (class "Default")
      (node (ref "CV_OUT") (pin "NORM") (pinfunction "NORM_NORM") (pintype "passive"))
    )
    (net (code "66") (name "unconnected-(TRIG_OUT-PadNORM)") (class "Default")
      (node (ref "TRIG_OUT") (pin "NORM") (pinfunction "NORM_NORM") (pintype "passive"))
    )
    (net (code "67") (name "unconnected-(U1-ADC6-Pad19)") (class "Default")
      (node (ref "U1") (pin "19") (pinfunction "ADC6_19") (pintype "bidirectional"))
    )
    (net (code "68") (name "unconnected-(U1-ADC7-Pad22)") (class "Default")
      (node (ref "U1") (pin "22") (pinfunction "ADC7_22") (pintype "bidirectional"))
    )
    (net (code "69") (name "unconnected-(U1-AREF-Pad20)") (class "Default")
      (node (ref "U1") (pin "20") (pinfunction "AREF_20") (pintype "bidirectional"))
    )
  )
)
